# me433_2021.net
KiCad netlist of a schematic drawn in EAGLE
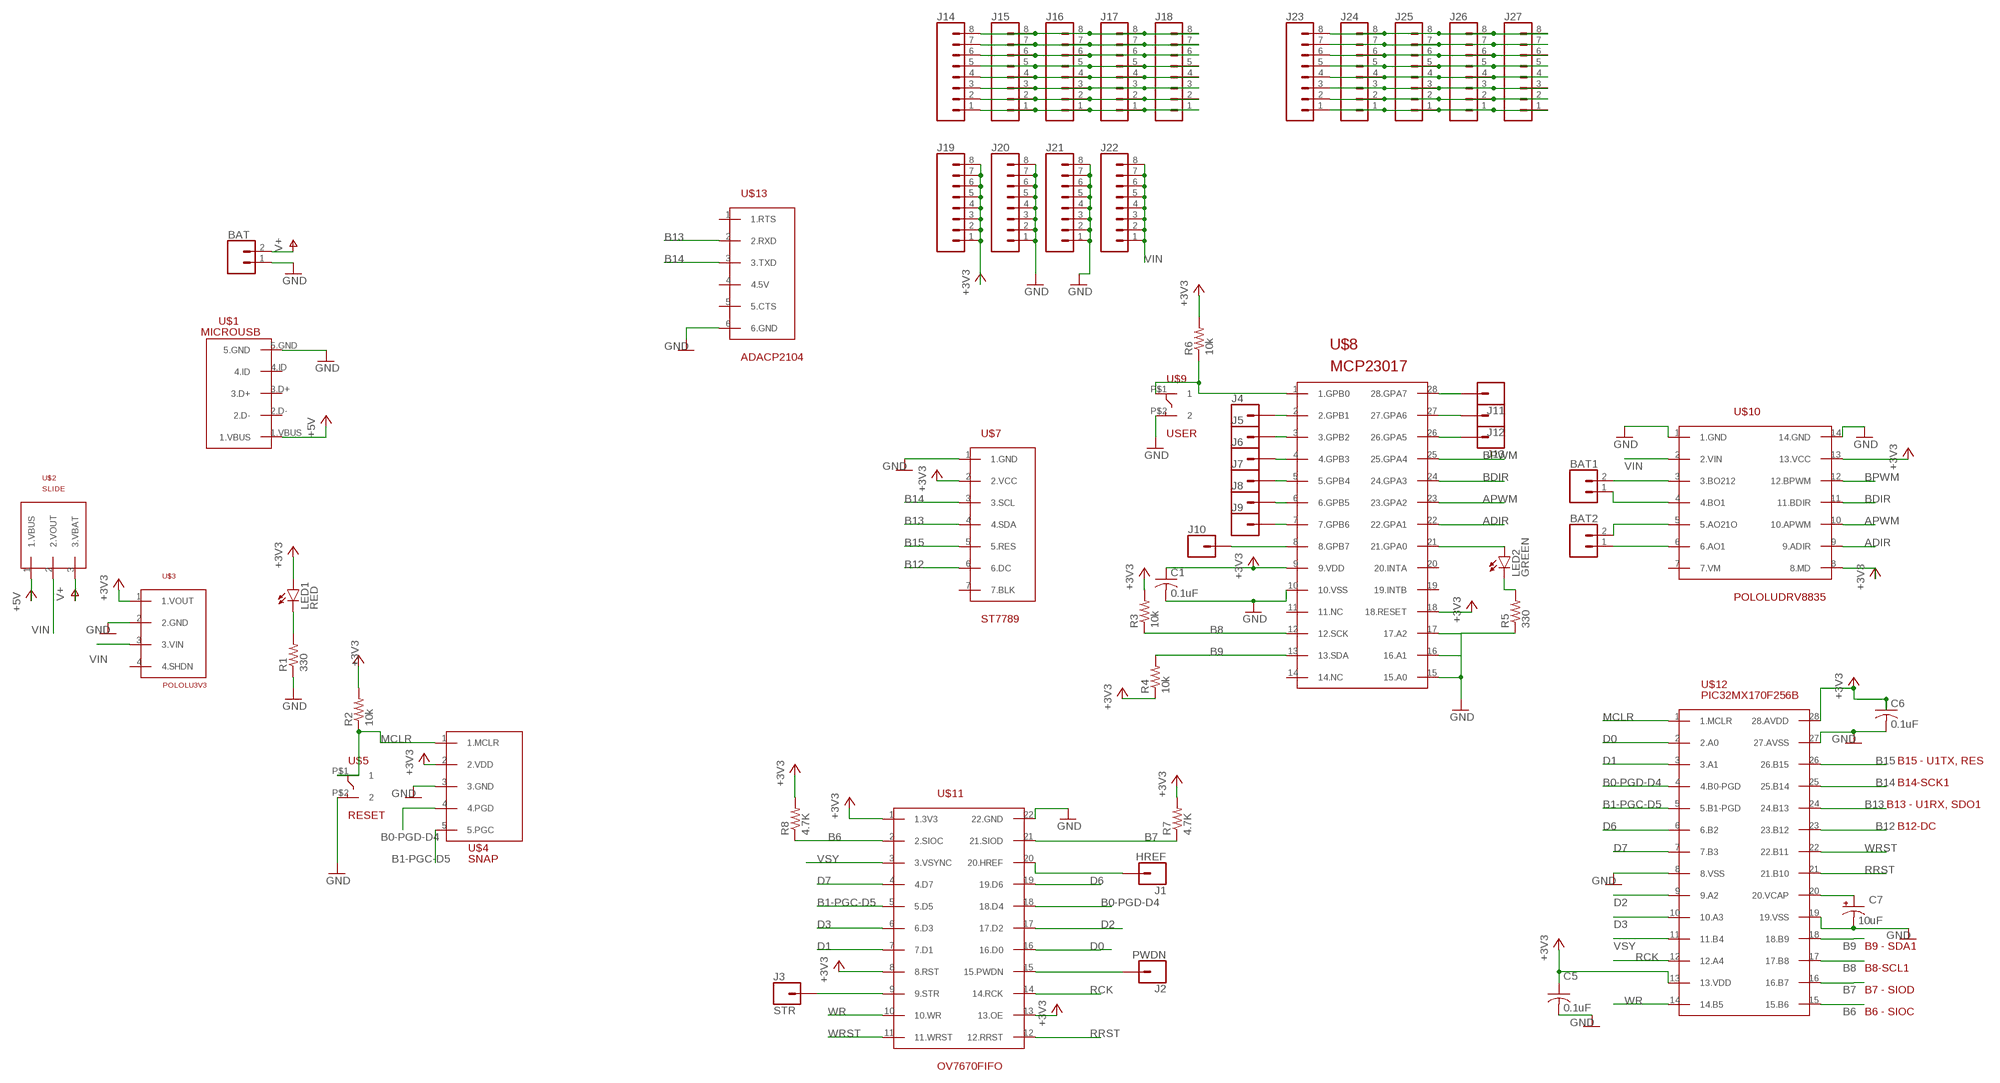
[diagram p0: schematic, sheet 1]

(export (version "E")
  (design (tool "Eeschema 10.0.6"))
  (components
    (comp (ref "BAT")
      (value "CONN_02")
      (footprint "eagle-import:1X02")
      (libsource (lib "eagle-import") (part "CONN_02"))
    )
    (comp (ref "BAT1")
      (value "CONN_02")
      (footprint "eagle-import:1X02")
      (libsource (lib "eagle-import") (part "CONN_02"))
    )
    (comp (ref "BAT2")
      (value "CONN_02")
      (footprint "eagle-import:1X02")
      (libsource (lib "eagle-import") (part "CONN_02"))
    )
    (comp (ref "C1")
      (value "0.1uF")
      (footprint "eagle-import:C025-030X050")
      (libsource (lib "eagle-import") (part "C-US025-030X050"))
    )
    (comp (ref "C5")
      (value "0.1uF")
      (footprint "eagle-import:C025-030X050")
      (libsource (lib "eagle-import") (part "C-US025-030X050"))
    )
    (comp (ref "C6")
      (value "0.1uF")
      (footprint "eagle-import:C025-030X050")
      (libsource (lib "eagle-import") (part "C-US025-030X050"))
    )
    (comp (ref "C7")
      (value "10uF")
      (footprint "eagle-import:B45181B")
      (libsource (lib "eagle-import") (part "CPOL-USB45181B"))
    )
    (comp (ref "J1")
      (value "HREF")
      (footprint "eagle-import:1X01")
      (libsource (lib "eagle-import") (part "CONN_01"))
    )
    (comp (ref "J2")
      (value "PWDN")
      (footprint "eagle-import:1X01")
      (libsource (lib "eagle-import") (part "CONN_01"))
    )
    (comp (ref "J3")
      (value "STR")
      (footprint "eagle-import:1X01")
      (libsource (lib "eagle-import") (part "CONN_01"))
    )
    (comp (ref "J4")
      (value "CONN_01")
      (footprint "eagle-import:1X01")
      (libsource (lib "eagle-import") (part "CONN_01"))
    )
    (comp (ref "J5")
      (value "CONN_01")
      (footprint "eagle-import:1X01")
      (libsource (lib "eagle-import") (part "CONN_01"))
    )
    (comp (ref "J6")
      (value "CONN_01")
      (footprint "eagle-import:1X01")
      (libsource (lib "eagle-import") (part "CONN_01"))
    )
    (comp (ref "J7")
      (value "CONN_01")
      (footprint "eagle-import:1X01")
      (libsource (lib "eagle-import") (part "CONN_01"))
    )
    (comp (ref "J8")
      (value "CONN_01")
      (footprint "eagle-import:1X01")
      (libsource (lib "eagle-import") (part "CONN_01"))
    )
    (comp (ref "J9")
      (value "CONN_01")
      (footprint "eagle-import:1X01")
      (libsource (lib "eagle-import") (part "CONN_01"))
    )
    (comp (ref "J10")
      (value "CONN_01")
      (footprint "eagle-import:1X01")
      (libsource (lib "eagle-import") (part "CONN_01"))
    )
    (comp (ref "J11")
      (value "CONN_01")
      (footprint "eagle-import:1X01")
      (libsource (lib "eagle-import") (part "CONN_01"))
    )
    (comp (ref "J12")
      (value "CONN_01")
      (footprint "eagle-import:1X01")
      (libsource (lib "eagle-import") (part "CONN_01"))
    )
    (comp (ref "J13")
      (value "CONN_01")
      (footprint "eagle-import:1X01")
      (libsource (lib "eagle-import") (part "CONN_01"))
    )
    (comp (ref "J14")
      (value "CONN_08\"")
      (footprint "eagle-import:1X08")
      (libsource (lib "eagle-import") (part "CONN_08{dblquote}"))
    )
    (comp (ref "J15")
      (value "CONN_08\"")
      (footprint "eagle-import:1X08")
      (libsource (lib "eagle-import") (part "CONN_08{dblquote}"))
    )
    (comp (ref "J16")
      (value "CONN_08\"")
      (footprint "eagle-import:1X08")
      (libsource (lib "eagle-import") (part "CONN_08{dblquote}"))
    )
    (comp (ref "J17")
      (value "CONN_08\"")
      (footprint "eagle-import:1X08")
      (libsource (lib "eagle-import") (part "CONN_08{dblquote}"))
    )
    (comp (ref "J18")
      (value "CONN_08\"")
      (footprint "eagle-import:1X08")
      (libsource (lib "eagle-import") (part "CONN_08{dblquote}"))
    )
    (comp (ref "J19")
      (value "CONN_08\"")
      (footprint "eagle-import:1X08")
      (libsource (lib "eagle-import") (part "CONN_08{dblquote}"))
    )
    (comp (ref "J20")
      (value "CONN_08\"")
      (footprint "eagle-import:1X08")
      (libsource (lib "eagle-import") (part "CONN_08{dblquote}"))
    )
    (comp (ref "J21")
      (value "CONN_08\"")
      (footprint "eagle-import:1X08")
      (libsource (lib "eagle-import") (part "CONN_08{dblquote}"))
    )
    (comp (ref "J22")
      (value "CONN_08\"")
      (footprint "eagle-import:1X08")
      (libsource (lib "eagle-import") (part "CONN_08{dblquote}"))
    )
    (comp (ref "J23")
      (value "CONN_08\"")
      (footprint "eagle-import:1X08")
      (libsource (lib "eagle-import") (part "CONN_08{dblquote}"))
    )
    (comp (ref "J24")
      (value "CONN_08\"")
      (footprint "eagle-import:1X08")
      (libsource (lib "eagle-import") (part "CONN_08{dblquote}"))
    )
    (comp (ref "J25")
      (value "CONN_08\"")
      (footprint "eagle-import:1X08")
      (libsource (lib "eagle-import") (part "CONN_08{dblquote}"))
    )
    (comp (ref "J26")
      (value "CONN_08\"")
      (footprint "eagle-import:1X08")
      (libsource (lib "eagle-import") (part "CONN_08{dblquote}"))
    )
    (comp (ref "J27")
      (value "CONN_08\"")
      (footprint "eagle-import:1X08")
      (libsource (lib "eagle-import") (part "CONN_08{dblquote}"))
    )
    (comp (ref "LED1")
      (value "RED")
      (footprint "eagle-import:LED3MM")
      (libsource (lib "eagle-import") (part "LED3MM"))
    )
    (comp (ref "LED2")
      (value "GREEN")
      (footprint "eagle-import:LED3MM")
      (libsource (lib "eagle-import") (part "LED3MM"))
    )
    (comp (ref "R1")
      (value "330")
      (footprint "eagle-import:0207_10")
      (libsource (lib "eagle-import") (part "R-US_0207/10"))
    )
    (comp (ref "R2")
      (value "10k")
      (footprint "eagle-import:0207_10")
      (libsource (lib "eagle-import") (part "R-US_0207/10"))
    )
    (comp (ref "R3")
      (value "10k")
      (footprint "eagle-import:0207_10")
      (libsource (lib "eagle-import") (part "R-US_0207/10"))
    )
    (comp (ref "R4")
      (value "10k")
      (footprint "eagle-import:0207_10")
      (libsource (lib "eagle-import") (part "R-US_0207/10"))
    )
    (comp (ref "R5")
      (value "330")
      (footprint "eagle-import:0207_10")
      (libsource (lib "eagle-import") (part "R-US_0207/10"))
    )
    (comp (ref "R6")
      (value "10k")
      (footprint "eagle-import:0207_10")
      (libsource (lib "eagle-import") (part "R-US_0207/10"))
    )
    (comp (ref "R7")
      (value "4.7K")
      (footprint "eagle-import:0207_10")
      (libsource (lib "eagle-import") (part "R-US_0207/10"))
    )
    (comp (ref "R8")
      (value "4.7K")
      (footprint "eagle-import:0207_10")
      (libsource (lib "eagle-import") (part "R-US_0207/10"))
    )
    (comp (ref "U$1")
      (value "MICROUSB")
      (footprint "eagle-import:MICROUSB")
      (libsource (lib "eagle-import") (part "MICROUSB"))
    )
    (comp (ref "U$2")
      (value "SLIDE")
      (footprint "eagle-import:SLIDE")
      (libsource (lib "eagle-import") (part "SLIDE"))
    )
    (comp (ref "U$3")
      (value "POLOLU3V3")
      (footprint "eagle-import:POLOLU3V3")
      (libsource (lib "eagle-import") (part "POLOLU3V3"))
    )
    (comp (ref "U$4")
      (value "SNAP")
      (footprint "eagle-import:SNAP")
      (libsource (lib "eagle-import") (part "SNAP"))
    )
    (comp (ref "U$5")
      (value "RESET")
      (footprint "eagle-import:PUSH")
      (libsource (lib "eagle-import") (part "PUSH"))
    )
    (comp (ref "U$7")
      (value "ST7789")
      (footprint "eagle-import:ST7789")
      (libsource (lib "eagle-import") (part "ST7789"))
    )
    (comp (ref "U$8")
      (value "MCP23017")
      (footprint "eagle-import:DIL28-3")
      (libsource (lib "eagle-import") (part "MCP23017"))
    )
    (comp (ref "U$9")
      (value "USER")
      (footprint "eagle-import:PUSH")
      (libsource (lib "eagle-import") (part "PUSH"))
    )
    (comp (ref "U$10")
      (value "POLOLUDRV8835")
      (footprint "eagle-import:DIL14")
      (libsource (lib "eagle-import") (part "POLOLUDRV8835"))
    )
    (comp (ref "U$11")
      (value "OV7670FIFO")
      (footprint "eagle-import:OV7670FIFO")
      (libsource (lib "eagle-import") (part "OV7670FIFO"))
    )
    (comp (ref "U$12")
      (value "PIC32MX170F256B")
      (footprint "eagle-import:DIL28-3")
      (libsource (lib "eagle-import") (part "PIC32MX170F256B"))
    )
    (comp (ref "U$13")
      (value "ADACP2104")
      (footprint "eagle-import:ADACP2104")
      (libsource (lib "eagle-import") (part "ADACP2104"))
    )
  )
  (nets
    (net (code "1") (name "+3V3") (class "Default")
      (node (ref "C1") (pin "1") (pinfunction "1_1") (pintype "passive"))
      (node (ref "C5") (pin "1") (pinfunction "1_1") (pintype "passive"))
      (node (ref "C6") (pin "1") (pinfunction "1_1") (pintype "passive"))
      (node (ref "J19") (pin "1") (pinfunction "1_1") (pintype "passive"))
      (node (ref "J19") (pin "2") (pinfunction "2_2") (pintype "passive"))
      (node (ref "J19") (pin "3") (pinfunction "3_3") (pintype "passive"))
      (node (ref "J19") (pin "4") (pinfunction "4_4") (pintype "passive"))
      (node (ref "J19") (pin "5") (pinfunction "5_5") (pintype "passive"))
      (node (ref "J19") (pin "6") (pinfunction "6_6") (pintype "passive"))
      (node (ref "J19") (pin "7") (pinfunction "7_7") (pintype "passive"))
      (node (ref "J19") (pin "8") (pinfunction "8_8") (pintype "passive"))
      (node (ref "LED1") (pin "A") (pinfunction "A_A") (pintype "passive"))
      (node (ref "R2") (pin "2") (pinfunction "2_2") (pintype "passive"))
      (node (ref "R3") (pin "2") (pinfunction "2_2") (pintype "passive"))
      (node (ref "R4") (pin "1") (pinfunction "1_1") (pintype "passive"))
      (node (ref "R6") (pin "2") (pinfunction "2_2") (pintype "passive"))
      (node (ref "R7") (pin "2") (pinfunction "2_2") (pintype "passive"))
      (node (ref "R8") (pin "2") (pinfunction "2_2") (pintype "passive"))
      (node (ref "U$10") (pin "13") (pinfunction "13.VCC_13") (pintype "bidirectional"))
      (node (ref "U$10") (pin "8") (pinfunction "8.MD_8") (pintype "bidirectional"))
      (node (ref "U$11") (pin "1") (pinfunction "1.3V3_1") (pintype "bidirectional"))
      (node (ref "U$11") (pin "13") (pinfunction "13.OE_13") (pintype "bidirectional"))
      (node (ref "U$11") (pin "8") (pinfunction "8.RST_8") (pintype "bidirectional"))
      (node (ref "U$12") (pin "13") (pinfunction "13.VDD_13") (pintype "bidirectional"))
      (node (ref "U$12") (pin "28") (pinfunction "28.AVDD_28") (pintype "bidirectional"))
      (node (ref "U$3") (pin "1") (pinfunction "1.VOUT_1") (pintype "bidirectional"))
      (node (ref "U$4") (pin "2") (pinfunction "2.VDD_2") (pintype "bidirectional"))
      (node (ref "U$7") (pin "2") (pinfunction "2.VCC_2") (pintype "bidirectional"))
      (node (ref "U$8") (pin "18") (pinfunction "18.RESET_18") (pintype "bidirectional"))
      (node (ref "U$8") (pin "9") (pinfunction "9.VDD_9") (pintype "bidirectional"))
    )
    (net (code "2") (name "+5V") (class "Default")
      (node (ref "U$1") (pin "1.VBUS") (pinfunction "1.VBUS_1.VBUS") (pintype "bidirectional"))
      (node (ref "U$2") (pin "1") (pinfunction "1.VBUS_1") (pintype "bidirectional"))
    )
    (net (code "3") (name "/ADIR") (class "Default")
      (node (ref "U$10") (pin "9") (pinfunction "9.ADIR_9") (pintype "bidirectional"))
      (node (ref "U$8") (pin "22") (pinfunction "22.GPA1_22") (pintype "bidirectional"))
    )
    (net (code "4") (name "/APWM") (class "Default")
      (node (ref "U$10") (pin "10") (pinfunction "10.APWM_10") (pintype "bidirectional"))
      (node (ref "U$8") (pin "23") (pinfunction "23.GPA2_23") (pintype "bidirectional"))
    )
    (net (code "5") (name "/B0-PGD-D4") (class "Default")
      (node (ref "U$11") (pin "18") (pinfunction "18.D4_18") (pintype "bidirectional"))
      (node (ref "U$12") (pin "4") (pinfunction "4.B0-PGD_4") (pintype "bidirectional"))
      (node (ref "U$4") (pin "4") (pinfunction "4.PGD_4") (pintype "bidirectional"))
    )
    (net (code "6") (name "/B1-PGC-D5") (class "Default")
      (node (ref "U$11") (pin "5") (pinfunction "5.D5_5") (pintype "bidirectional"))
      (node (ref "U$12") (pin "5") (pinfunction "5.B1-PGD_5") (pintype "bidirectional"))
      (node (ref "U$4") (pin "5") (pinfunction "5.PGC_5") (pintype "bidirectional"))
    )
    (net (code "7") (name "/B6") (class "Default")
      (node (ref "R8") (pin "1") (pinfunction "1_1") (pintype "passive"))
      (node (ref "U$11") (pin "2") (pinfunction "2.SIOC_2") (pintype "bidirectional"))
      (node (ref "U$12") (pin "15") (pinfunction "15.B6_15") (pintype "bidirectional"))
    )
    (net (code "8") (name "/B7") (class "Default")
      (node (ref "R7") (pin "1") (pinfunction "1_1") (pintype "passive"))
      (node (ref "U$11") (pin "21") (pinfunction "21.SIOD_21") (pintype "bidirectional"))
      (node (ref "U$12") (pin "16") (pinfunction "16.B7_16") (pintype "bidirectional"))
    )
    (net (code "9") (name "/B8") (class "Default")
      (node (ref "R3") (pin "1") (pinfunction "1_1") (pintype "passive"))
      (node (ref "U$12") (pin "17") (pinfunction "17.B8_17") (pintype "bidirectional"))
      (node (ref "U$8") (pin "12") (pinfunction "12.SCK_12") (pintype "bidirectional"))
    )
    (net (code "10") (name "/B9") (class "Default")
      (node (ref "R4") (pin "2") (pinfunction "2_2") (pintype "passive"))
      (node (ref "U$12") (pin "18") (pinfunction "18.B9_18") (pintype "bidirectional"))
      (node (ref "U$8") (pin "13") (pinfunction "13.SDA_13") (pintype "bidirectional"))
    )
    (net (code "11") (name "/B12") (class "Default")
      (node (ref "U$12") (pin "23") (pinfunction "23.B12_23") (pintype "bidirectional"))
      (node (ref "U$7") (pin "6") (pinfunction "6.DC_6") (pintype "bidirectional"))
    )
    (net (code "12") (name "/B13") (class "Default")
      (node (ref "U$12") (pin "24") (pinfunction "24.B13_24") (pintype "bidirectional"))
      (node (ref "U$13") (pin "2") (pinfunction "2.RXD_2") (pintype "bidirectional"))
      (node (ref "U$7") (pin "4") (pinfunction "4.SDA_4") (pintype "bidirectional"))
    )
    (net (code "13") (name "/B14") (class "Default")
      (node (ref "U$12") (pin "25") (pinfunction "25.B14_25") (pintype "bidirectional"))
      (node (ref "U$13") (pin "3") (pinfunction "3.TXD_3") (pintype "bidirectional"))
      (node (ref "U$7") (pin "3") (pinfunction "3.SCL_3") (pintype "bidirectional"))
    )
    (net (code "14") (name "/B15") (class "Default")
      (node (ref "U$12") (pin "26") (pinfunction "26.B15_26") (pintype "bidirectional"))
      (node (ref "U$7") (pin "5") (pinfunction "5.RES_5") (pintype "bidirectional"))
    )
    (net (code "15") (name "/BDIR") (class "Default")
      (node (ref "U$10") (pin "11") (pinfunction "11.BDIR_11") (pintype "bidirectional"))
      (node (ref "U$8") (pin "24") (pinfunction "24.GPA3_24") (pintype "bidirectional"))
    )
    (net (code "16") (name "/BPWM") (class "Default")
      (node (ref "U$10") (pin "12") (pinfunction "12.BPWM_12") (pintype "bidirectional"))
      (node (ref "U$8") (pin "25") (pinfunction "25.GPA4_25") (pintype "bidirectional"))
    )
    (net (code "17") (name "/D0") (class "Default")
      (node (ref "U$11") (pin "16") (pinfunction "16.D0_16") (pintype "bidirectional"))
      (node (ref "U$12") (pin "2") (pinfunction "2.A0_2") (pintype "bidirectional"))
    )
    (net (code "18") (name "/D1") (class "Default")
      (node (ref "U$11") (pin "7") (pinfunction "7.D1_7") (pintype "bidirectional"))
      (node (ref "U$12") (pin "3") (pinfunction "3.A1_3") (pintype "bidirectional"))
    )
    (net (code "19") (name "/D2") (class "Default")
      (node (ref "U$11") (pin "17") (pinfunction "17.D2_17") (pintype "bidirectional"))
      (node (ref "U$12") (pin "9") (pinfunction "9.A2_9") (pintype "bidirectional"))
    )
    (net (code "20") (name "/D3") (class "Default")
      (node (ref "U$11") (pin "6") (pinfunction "6.D3_6") (pintype "bidirectional"))
      (node (ref "U$12") (pin "10") (pinfunction "10.A3_10") (pintype "bidirectional"))
    )
    (net (code "21") (name "/D6") (class "Default")
      (node (ref "U$11") (pin "19") (pinfunction "19.D6_19") (pintype "bidirectional"))
      (node (ref "U$12") (pin "6") (pinfunction "6.B2_6") (pintype "bidirectional"))
    )
    (net (code "22") (name "/D7") (class "Default")
      (node (ref "U$11") (pin "4") (pinfunction "4.D7_4") (pintype "bidirectional"))
      (node (ref "U$12") (pin "7") (pinfunction "7.B3_7") (pintype "bidirectional"))
    )
    (net (code "23") (name "/MCLR") (class "Default")
      (node (ref "R2") (pin "1") (pinfunction "1_1") (pintype "passive"))
      (node (ref "U$12") (pin "1") (pinfunction "1.MCLR_1") (pintype "bidirectional"))
      (node (ref "U$4") (pin "1") (pinfunction "1.MCLR_1") (pintype "bidirectional"))
      (node (ref "U$5") (pin "P$1") (pinfunction "1_P$1") (pintype "bidirectional"))
    )
    (net (code "24") (name "/RCK") (class "Default")
      (node (ref "U$11") (pin "14") (pinfunction "14.RCK_14") (pintype "bidirectional"))
      (node (ref "U$12") (pin "12") (pinfunction "12.A4_12") (pintype "bidirectional"))
    )
    (net (code "25") (name "/RRST") (class "Default")
      (node (ref "U$11") (pin "12") (pinfunction "12.RRST_12") (pintype "bidirectional"))
      (node (ref "U$12") (pin "21") (pinfunction "21.B10_21") (pintype "bidirectional"))
    )
    (net (code "26") (name "/VIN") (class "Default")
      (node (ref "J22") (pin "1") (pinfunction "1_1") (pintype "passive"))
      (node (ref "J22") (pin "2") (pinfunction "2_2") (pintype "passive"))
      (node (ref "J22") (pin "3") (pinfunction "3_3") (pintype "passive"))
      (node (ref "J22") (pin "4") (pinfunction "4_4") (pintype "passive"))
      (node (ref "J22") (pin "5") (pinfunction "5_5") (pintype "passive"))
      (node (ref "J22") (pin "6") (pinfunction "6_6") (pintype "passive"))
      (node (ref "J22") (pin "7") (pinfunction "7_7") (pintype "passive"))
      (node (ref "J22") (pin "8") (pinfunction "8_8") (pintype "passive"))
      (node (ref "U$10") (pin "2") (pinfunction "2.VIN_2") (pintype "bidirectional"))
      (node (ref "U$2") (pin "2") (pinfunction "2.VOUT_2") (pintype "bidirectional"))
      (node (ref "U$3") (pin "3") (pinfunction "3.VIN_3") (pintype "bidirectional"))
    )
    (net (code "27") (name "/VSY") (class "Default")
      (node (ref "U$11") (pin "3") (pinfunction "3.VSYNC_3") (pintype "bidirectional"))
      (node (ref "U$12") (pin "11") (pinfunction "11.B4_11") (pintype "bidirectional"))
    )
    (net (code "28") (name "/WR") (class "Default")
      (node (ref "U$11") (pin "10") (pinfunction "10.WR_10") (pintype "bidirectional"))
      (node (ref "U$12") (pin "14") (pinfunction "14.B5_14") (pintype "bidirectional"))
    )
    (net (code "29") (name "/WRST") (class "Default")
      (node (ref "U$11") (pin "11") (pinfunction "11.WRST_11") (pintype "bidirectional"))
      (node (ref "U$12") (pin "22") (pinfunction "22.B11_22") (pintype "bidirectional"))
    )
    (net (code "30") (name "GND") (class "Default")
      (node (ref "BAT") (pin "1") (pinfunction "1_1") (pintype "passive"))
      (node (ref "C1") (pin "2") (pinfunction "2_2") (pintype "passive"))
      (node (ref "C5") (pin "2") (pinfunction "2_2") (pintype "passive"))
      (node (ref "C6") (pin "2") (pinfunction "2_2") (pintype "passive"))
      (node (ref "C7") (pin "-") (pinfunction "-_-") (pintype "passive"))
      (node (ref "J20") (pin "1") (pinfunction "1_1") (pintype "passive"))
      (node (ref "J20") (pin "2") (pinfunction "2_2") (pintype "passive"))
      (node (ref "J20") (pin "3") (pinfunction "3_3") (pintype "passive"))
      (node (ref "J20") (pin "4") (pinfunction "4_4") (pintype "passive"))
      (node (ref "J20") (pin "5") (pinfunction "5_5") (pintype "passive"))
      (node (ref "J20") (pin "6") (pinfunction "6_6") (pintype "passive"))
      (node (ref "J20") (pin "7") (pinfunction "7_7") (pintype "passive"))
      (node (ref "J20") (pin "8") (pinfunction "8_8") (pintype "passive"))
      (node (ref "J21") (pin "1") (pinfunction "1_1") (pintype "passive"))
      (node (ref "J21") (pin "2") (pinfunction "2_2") (pintype "passive"))
      (node (ref "J21") (pin "3") (pinfunction "3_3") (pintype "passive"))
      (node (ref "J21") (pin "4") (pinfunction "4_4") (pintype "passive"))
      (node (ref "J21") (pin "5") (pinfunction "5_5") (pintype "passive"))
      (node (ref "J21") (pin "6") (pinfunction "6_6") (pintype "passive"))
      (node (ref "J21") (pin "7") (pinfunction "7_7") (pintype "passive"))
      (node (ref "J21") (pin "8") (pinfunction "8_8") (pintype "passive"))
      (node (ref "R1") (pin "1") (pinfunction "1_1") (pintype "passive"))
      (node (ref "R5") (pin "1") (pinfunction "1_1") (pintype "passive"))
      (node (ref "U$1") (pin "5.GND") (pinfunction "5.GND_5.GND") (pintype "bidirectional"))
      (node (ref "U$10") (pin "1") (pinfunction "1.GND_1") (pintype "bidirectional"))
      (node (ref "U$10") (pin "14") (pinfunction "14.GND_14") (pintype "bidirectional"))
      (node (ref "U$11") (pin "22") (pinfunction "22.GND_22") (pintype "bidirectional"))
      (node (ref "U$12") (pin "19") (pinfunction "19.VSS_19") (pintype "bidirectional"))
      (node (ref "U$12") (pin "27") (pinfunction "27.AVSS_27") (pintype "bidirectional"))
      (node (ref "U$12") (pin "8") (pinfunction "8.VSS_8") (pintype "bidirectional"))
      (node (ref "U$13") (pin "6") (pinfunction "6.GND_6") (pintype "bidirectional"))
      (node (ref "U$3") (pin "2") (pinfunction "2.GND_2") (pintype "bidirectional"))
      (node (ref "U$4") (pin "3") (pinfunction "3.GND_3") (pintype "bidirectional"))
      (node (ref "U$5") (pin "P$2") (pinfunction "2_P$2") (pintype "bidirectional"))
      (node (ref "U$7") (pin "1") (pinfunction "1.GND_1") (pintype "bidirectional"))
      (node (ref "U$8") (pin "10") (pinfunction "10.VSS_10") (pintype "bidirectional"))
      (node (ref "U$8") (pin "15") (pinfunction "15.A0_15") (pintype "bidirectional"))
      (node (ref "U$8") (pin "16") (pinfunction "16.A1_16") (pintype "bidirectional"))
      (node (ref "U$8") (pin "17") (pinfunction "17.A2_17") (pintype "bidirectional"))
      (node (ref "U$9") (pin "P$2") (pinfunction "2_P$2") (pintype "bidirectional"))
    )
    (net (code "31") (name "Net-(J14-Pad1)") (class "Default")
      (node (ref "J14") (pin "1") (pinfunction "1_1") (pintype "passive"))
      (node (ref "J15") (pin "1") (pinfunction "1_1") (pintype "passive"))
      (node (ref "J16") (pin "1") (pinfunction "1_1") (pintype "passive"))
      (node (ref "J17") (pin "1") (pinfunction "1_1") (pintype "passive"))
      (node (ref "J18") (pin "1") (pinfunction "1_1") (pintype "passive"))
    )
    (net (code "32") (name "Net-(J14-Pad2)") (class "Default")
      (node (ref "J14") (pin "2") (pinfunction "2_2") (pintype "passive"))
      (node (ref "J15") (pin "2") (pinfunction "2_2") (pintype "passive"))
      (node (ref "J16") (pin "2") (pinfunction "2_2") (pintype "passive"))
      (node (ref "J17") (pin "2") (pinfunction "2_2") (pintype "passive"))
      (node (ref "J18") (pin "2") (pinfunction "2_2") (pintype "passive"))
    )
    (net (code "33") (name "Net-(J14-Pad3)") (class "Default")
      (node (ref "J14") (pin "3") (pinfunction "3_3") (pintype "passive"))
      (node (ref "J15") (pin "3") (pinfunction "3_3") (pintype "passive"))
      (node (ref "J16") (pin "3") (pinfunction "3_3") (pintype "passive"))
      (node (ref "J17") (pin "3") (pinfunction "3_3") (pintype "passive"))
      (node (ref "J18") (pin "3") (pinfunction "3_3") (pintype "passive"))
    )
    (net (code "34") (name "Net-(J14-Pad4)") (class "Default")
      (node (ref "J14") (pin "4") (pinfunction "4_4") (pintype "passive"))
      (node (ref "J15") (pin "4") (pinfunction "4_4") (pintype "passive"))
      (node (ref "J16") (pin "4") (pinfunction "4_4") (pintype "passive"))
      (node (ref "J17") (pin "4") (pinfunction "4_4") (pintype "passive"))
      (node (ref "J18") (pin "4") (pinfunction "4_4") (pintype "passive"))
    )
    (net (code "35") (name "Net-(J14-Pad5)") (class "Default")
      (node (ref "J14") (pin "5") (pinfunction "5_5") (pintype "passive"))
      (node (ref "J15") (pin "5") (pinfunction "5_5") (pintype "passive"))
      (node (ref "J16") (pin "5") (pinfunction "5_5") (pintype "passive"))
      (node (ref "J17") (pin "5") (pinfunction "5_5") (pintype "passive"))
      (node (ref "J18") (pin "5") (pinfunction "5_5") (pintype "passive"))
    )
    (net (code "36") (name "Net-(J14-Pad6)") (class "Default")
      (node (ref "J14") (pin "6") (pinfunction "6_6") (pintype "passive"))
      (node (ref "J15") (pin "6") (pinfunction "6_6") (pintype "passive"))
      (node (ref "J16") (pin "6") (pinfunction "6_6") (pintype "passive"))
      (node (ref "J17") (pin "6") (pinfunction "6_6") (pintype "passive"))
      (node (ref "J18") (pin "6") (pinfunction "6_6") (pintype "passive"))
    )
    (net (code "37") (name "Net-(J14-Pad7)") (class "Default")
      (node (ref "J14") (pin "7") (pinfunction "7_7") (pintype "passive"))
      (node (ref "J15") (pin "7") (pinfunction "7_7") (pintype "passive"))
      (node (ref "J16") (pin "7") (pinfunction "7_7") (pintype "passive"))
      (node (ref "J17") (pin "7") (pinfunction "7_7") (pintype "passive"))
      (node (ref "J18") (pin "7") (pinfunction "7_7") (pintype "passive"))
    )
    (net (code "38") (name "Net-(J14-Pad8)") (class "Default")
      (node (ref "J14") (pin "8") (pinfunction "8_8") (pintype "passive"))
      (node (ref "J15") (pin "8") (pinfunction "8_8") (pintype "passive"))
      (node (ref "J16") (pin "8") (pinfunction "8_8") (pintype "passive"))
      (node (ref "J17") (pin "8") (pinfunction "8_8") (pintype "passive"))
      (node (ref "J18") (pin "8") (pinfunction "8_8") (pintype "passive"))
    )
    (net (code "39") (name "Net-(J23-Pad1)") (class "Default")
      (node (ref "J23") (pin "1") (pinfunction "1_1") (pintype "passive"))
      (node (ref "J24") (pin "1") (pinfunction "1_1") (pintype "passive"))
      (node (ref "J25") (pin "1") (pinfunction "1_1") (pintype "passive"))
      (node (ref "J26") (pin "1") (pinfunction "1_1") (pintype "passive"))
      (node (ref "J27") (pin "1") (pinfunction "1_1") (pintype "passive"))
    )
    (net (code "40") (name "Net-(J23-Pad2)") (class "Default")
      (node (ref "J23") (pin "2") (pinfunction "2_2") (pintype "passive"))
      (node (ref "J24") (pin "2") (pinfunction "2_2") (pintype "passive"))
      (node (ref "J25") (pin "2") (pinfunction "2_2") (pintype "passive"))
      (node (ref "J26") (pin "2") (pinfunction "2_2") (pintype "passive"))
      (node (ref "J27") (pin "2") (pinfunction "2_2") (pintype "passive"))
    )
    (net (code "41") (name "Net-(J23-Pad3)") (class "Default")
      (node (ref "J23") (pin "3") (pinfunction "3_3") (pintype "passive"))
      (node (ref "J24") (pin "3") (pinfunction "3_3") (pintype "passive"))
      (node (ref "J25") (pin "3") (pinfunction "3_3") (pintype "passive"))
      (node (ref "J26") (pin "3") (pinfunction "3_3") (pintype "passive"))
      (node (ref "J27") (pin "3") (pinfunction "3_3") (pintype "passive"))
    )
    (net (code "42") (name "Net-(J23-Pad4)") (class "Default")
      (node (ref "J23") (pin "4") (pinfunction "4_4") (pintype "passive"))
      (node (ref "J24") (pin "4") (pinfunction "4_4") (pintype "passive"))
      (node (ref "J25") (pin "4") (pinfunction "4_4") (pintype "passive"))
      (node (ref "J26") (pin "4") (pinfunction "4_4") (pintype "passive"))
      (node (ref "J27") (pin "4") (pinfunction "4_4") (pintype "passive"))
    )
    (net (code "43") (name "Net-(J23-Pad5)") (class "Default")
      (node (ref "J23") (pin "5") (pinfunction "5_5") (pintype "passive"))
      (node (ref "J24") (pin "5") (pinfunction "5_5") (pintype "passive"))
      (node (ref "J25") (pin "5") (pinfunction "5_5") (pintype "passive"))
      (node (ref "J26") (pin "5") (pinfunction "5_5") (pintype "passive"))
      (node (ref "J27") (pin "5") (pinfunction "5_5") (pintype "passive"))
    )
    (net (code "44") (name "Net-(J23-Pad6)") (class "Default")
      (node (ref "J23") (pin "6") (pinfunction "6_6") (pintype "passive"))
      (node (ref "J24") (pin "6") (pinfunction "6_6") (pintype "passive"))
      (node (ref "J25") (pin "6") (pinfunction "6_6") (pintype "passive"))
      (node (ref "J26") (pin "6") (pinfunction "6_6") (pintype "passive"))
      (node (ref "J27") (pin "6") (pinfunction "6_6") (pintype "passive"))
    )
    (net (code "45") (name "Net-(J23-Pad7)") (class "Default")
      (node (ref "J23") (pin "7") (pinfunction "7_7") (pintype "passive"))
      (node (ref "J24") (pin "7") (pinfunction "7_7") (pintype "passive"))
      (node (ref "J25") (pin "7") (pinfunction "7_7") (pintype "passive"))
      (node (ref "J26") (pin "7") (pinfunction "7_7") (pintype "passive"))
      (node (ref "J27") (pin "7") (pinfunction "7_7") (pintype "passive"))
    )
    (net (code "46") (name "Net-(J23-Pad8)") (class "Default")
      (node (ref "J23") (pin "8") (pinfunction "8_8") (pintype "passive"))
      (node (ref "J24") (pin "8") (pinfunction "8_8") (pintype "passive"))
      (node (ref "J25") (pin "8") (pinfunction "8_8") (pintype "passive"))
      (node (ref "J26") (pin "8") (pinfunction "8_8") (pintype "passive"))
      (node (ref "J27") (pin "8") (pinfunction "8_8") (pintype "passive"))
    )
    (net (code "47") (name "Net-(LED1-C)") (class "Default")
      (node (ref "LED1") (pin "K") (pinfunction "C_K") (pintype "passive"))
      (node (ref "R1") (pin "2") (pinfunction "2_2") (pintype "passive"))
    )
    (net (code "48") (name "Net-(LED2-C)") (class "Default")
      (node (ref "LED2") (pin "K") (pinfunction "C_K") (pintype "passive"))
      (node (ref "R5") (pin "2") (pinfunction "2_2") (pintype "passive"))
    )
    (net (code "49") (name "Net-(U$8-1.GPB0)") (class "Default")
      (node (ref "R6") (pin "1") (pinfunction "1_1") (pintype "passive"))
      (node (ref "U$8") (pin "1") (pinfunction "1.GPB0_1") (pintype "bidirectional"))
      (node (ref "U$9") (pin "P$1") (pinfunction "1_P$1") (pintype "bidirectional"))
    )
    (net (code "50") (name "Net-(U$8-2.GPB1)") (class "Default")
      (node (ref "J4") (pin "1") (pinfunction "1_1") (pintype "passive"))
      (node (ref "U$8") (pin "2") (pinfunction "2.GPB1_2") (pintype "bidirectional"))
    )
    (net (code "51") (name "Net-(U$8-3.GPB2)") (class "Default")
      (node (ref "J5") (pin "1") (pinfunction "1_1") (pintype "passive"))
      (node (ref "U$8") (pin "3") (pinfunction "3.GPB2_3") (pintype "bidirectional"))
    )
    (net (code "52") (name "Net-(U$8-4.GPB3)") (class "Default")
      (node (ref "J6") (pin "1") (pinfunction "1_1") (pintype "passive"))
      (node (ref "U$8") (pin "4") (pinfunction "4.GPB3_4") (pintype "bidirectional"))
    )
    (net (code "53") (name "Net-(U$8-5.GPB4)") (class "Default")
      (node (ref "J7") (pin "1") (pinfunction "1_1") (pintype "passive"))
      (node (ref "U$8") (pin "5") (pinfunction "5.GPB4_5") (pintype "bidirectional"))
    )
    (net (code "54") (name "Net-(U$8-6.GPB5)") (class "Default")
      (node (ref "J8") (pin "1") (pinfunction "1_1") (pintype "passive"))
      (node (ref "U$8") (pin "6") (pinfunction "6.GPB5_6") (pintype "bidirectional"))
    )
    (net (code "55") (name "Net-(U$8-7.GPB6)") (class "Default")
      (node (ref "J9") (pin "1") (pinfunction "1_1") (pintype "passive"))
      (node (ref "U$8") (pin "7") (pinfunction "7.GPB6_7") (pintype "bidirectional"))
    )
    (net (code "56") (name "Net-(U$8-8.GPB7)") (class "Default")
      (node (ref "J10") (pin "1") (pinfunction "1_1") (pintype "passive"))
      (node (ref "U$8") (pin "8") (pinfunction "8.GPB7_8") (pintype "bidirectional"))
    )
    (net (code "57") (name "Net-(U$8-21.GPA0)") (class "Default")
      (node (ref "LED2") (pin "A") (pinfunction "A_A") (pintype "passive"))
      (node (ref "U$8") (pin "21") (pinfunction "21.GPA0_21") (pintype "bidirectional"))
    )
    (net (code "58") (name "Net-(U$8-26.GPA5)") (class "Default")
      (node (ref "J13") (pin "1") (pinfunction "1_1") (pintype "passive"))
      (node (ref "U$8") (pin "26") (pinfunction "26.GPA5_26") (pintype "bidirectional"))
    )
    (net (code "59") (name "Net-(U$8-27.GPA6)") (class "Default")
      (node (ref "J12") (pin "1") (pinfunction "1_1") (pintype "passive"))
      (node (ref "U$8") (pin "27") (pinfunction "27.GPA6_27") (pintype "bidirectional"))
    )
    (net (code "60") (name "Net-(U$8-28.GPA7)") (class "Default")
      (node (ref "J11") (pin "1") (pinfunction "1_1") (pintype "passive"))
      (node (ref "U$8") (pin "28") (pinfunction "28.GPA7_28") (pintype "bidirectional"))
    )
    (net (code "61") (name "Net-(U$10-3.BO212)") (class "Default")
      (node (ref "BAT1") (pin "2") (pinfunction "2_2") (pintype "passive"))
      (node (ref "U$10") (pin "3") (pinfunction "3.BO212_3") (pintype "bidirectional"))
    )
    (net (code "62") (name "Net-(U$10-4.BO1)") (class "Default")
      (node (ref "BAT1") (pin "1") (pinfunction "1_1") (pintype "passive"))
      (node (ref "U$10") (pin "4") (pinfunction "4.BO1_4") (pintype "bidirectional"))
    )
    (net (code "63") (name "Net-(U$10-5.AO21O)") (class "Default")
      (node (ref "BAT2") (pin "2") (pinfunction "2_2") (pintype "passive"))
      (node (ref "U$10") (pin "5") (pinfunction "5.AO21O_5") (pintype "bidirectional"))
    )
    (net (code "64") (name "Net-(U$10-6.AO1)") (class "Default")
      (node (ref "BAT2") (pin "1") (pinfunction "1_1") (pintype "passive"))
      (node (ref "U$10") (pin "6") (pinfunction "6.AO1_6") (pintype "bidirectional"))
    )
    (net (code "65") (name "Net-(U$11-9.STR)") (class "Default")
      (node (ref "J3") (pin "1") (pinfunction "1_1") (pintype "passive"))
      (node (ref "U$11") (pin "9") (pinfunction "9.STR_9") (pintype "bidirectional"))
    )
    (net (code "66") (name "Net-(U$11-15.PWDN)") (class "Default")
      (node (ref "J2") (pin "1") (pinfunction "1_1") (pintype "passive"))
      (node (ref "U$11") (pin "15") (pinfunction "15.PWDN_15") (pintype "bidirectional"))
    )
    (net (code "67") (name "Net-(U$11-20.HREF)") (class "Default")
      (node (ref "J1") (pin "1") (pinfunction "1_1") (pintype "passive"))
      (node (ref "U$11") (pin "20") (pinfunction "20.HREF_20") (pintype "bidirectional"))
    )
    (net (code "68") (name "Net-(U$12-20.VCAP)") (class "Default")
      (node (ref "C7") (pin "+") (pinfunction "+_+") (pintype "passive"))
      (node (ref "U$12") (pin "20") (pinfunction "20.VCAP_20") (pintype "bidirectional"))
    )
    (net (code "69") (name "V+") (class "Default")
      (node (ref "BAT") (pin "2") (pinfunction "2_2") (pintype "passive"))
      (node (ref "U$2") (pin "3") (pinfunction "3.VBAT_3") (pintype "bidirectional"))
    )
    (net (code "70") (name "unconnected-(U$1-Pad2.D-)") (class "Default")
      (node (ref "U$1") (pin "2.D-") (pinfunction "2.D-_2.D-") (pintype "bidirectional"))
    )
    (net (code "71") (name "unconnected-(U$1-Pad3.D+)") (class "Default")
      (node (ref "U$1") (pin "3.D+") (pinfunction "3.D+_3.D+") (pintype "bidirectional"))
    )
    (net (code "72") (name "unconnected-(U$1-Pad4.ID)") (class "Default")
      (node (ref "U$1") (pin "4.ID") (pinfunction "4.ID_4.ID") (pintype "bidirectional"))
    )
    (net (code "73") (name "unconnected-(U$3-4.SHDN-Pad4)") (class "Default")
      (node (ref "U$3") (pin "4") (pinfunction "4.SHDN_4") (pintype "bidirectional"))
    )
    (net (code "74") (name "unconnected-(U$7-7.BLK-Pad7)") (class "Default")
      (node (ref "U$7") (pin "7") (pinfunction "7.BLK_7") (pintype "bidirectional"))
    )
    (net (code "75") (name "unconnected-(U$8-11.NC-Pad11)") (class "Default")
      (node (ref "U$8") (pin "11") (pinfunction "11.NC_11") (pintype "bidirectional"))
    )
    (net (code "76") (name "unconnected-(U$8-14.NC-Pad14)") (class "Default")
      (node (ref "U$8") (pin "14") (pinfunction "14.NC_14") (pintype "bidirectional"))
    )
    (net (code "77") (name "unconnected-(U$8-19.INTB-Pad19)") (class "Default")
      (node (ref "U$8") (pin "19") (pinfunction "19.INTB_19") (pintype "bidirectional"))
    )
    (net (code "78") (name "unconnected-(U$8-20.INTA-Pad20)") (class "Default")
      (node (ref "U$8") (pin "20") (pinfunction "20.INTA_20") (pintype "bidirectional"))
    )
    (net (code "79") (name "unconnected-(U$10-7.VM-Pad7)") (class "Default")
      (node (ref "U$10") (pin "7") (pinfunction "7.VM_7") (pintype "bidirectional"))
    )
    (net (code "80") (name "unconnected-(U$13-1.RTS-Pad1)") (class "Default")
      (node (ref "U$13") (pin "1") (pinfunction "1.RTS_1") (pintype "bidirectional"))
    )
    (net (code "81") (name "unconnected-(U$13-4.5V-Pad4)") (class "Default")
      (node (ref "U$13") (pin "4") (pinfunction "4.5V_4") (pintype "bidirectional"))
    )
    (net (code "82") (name "unconnected-(U$13-5.CTS-Pad5)") (class "Default")
      (node (ref "U$13") (pin "5") (pinfunction "5.CTS_5") (pintype "bidirectional"))
    )
  )
)
